# Sch1r2_new.net
KiCad netlist of a schematic drawn in EAGLE
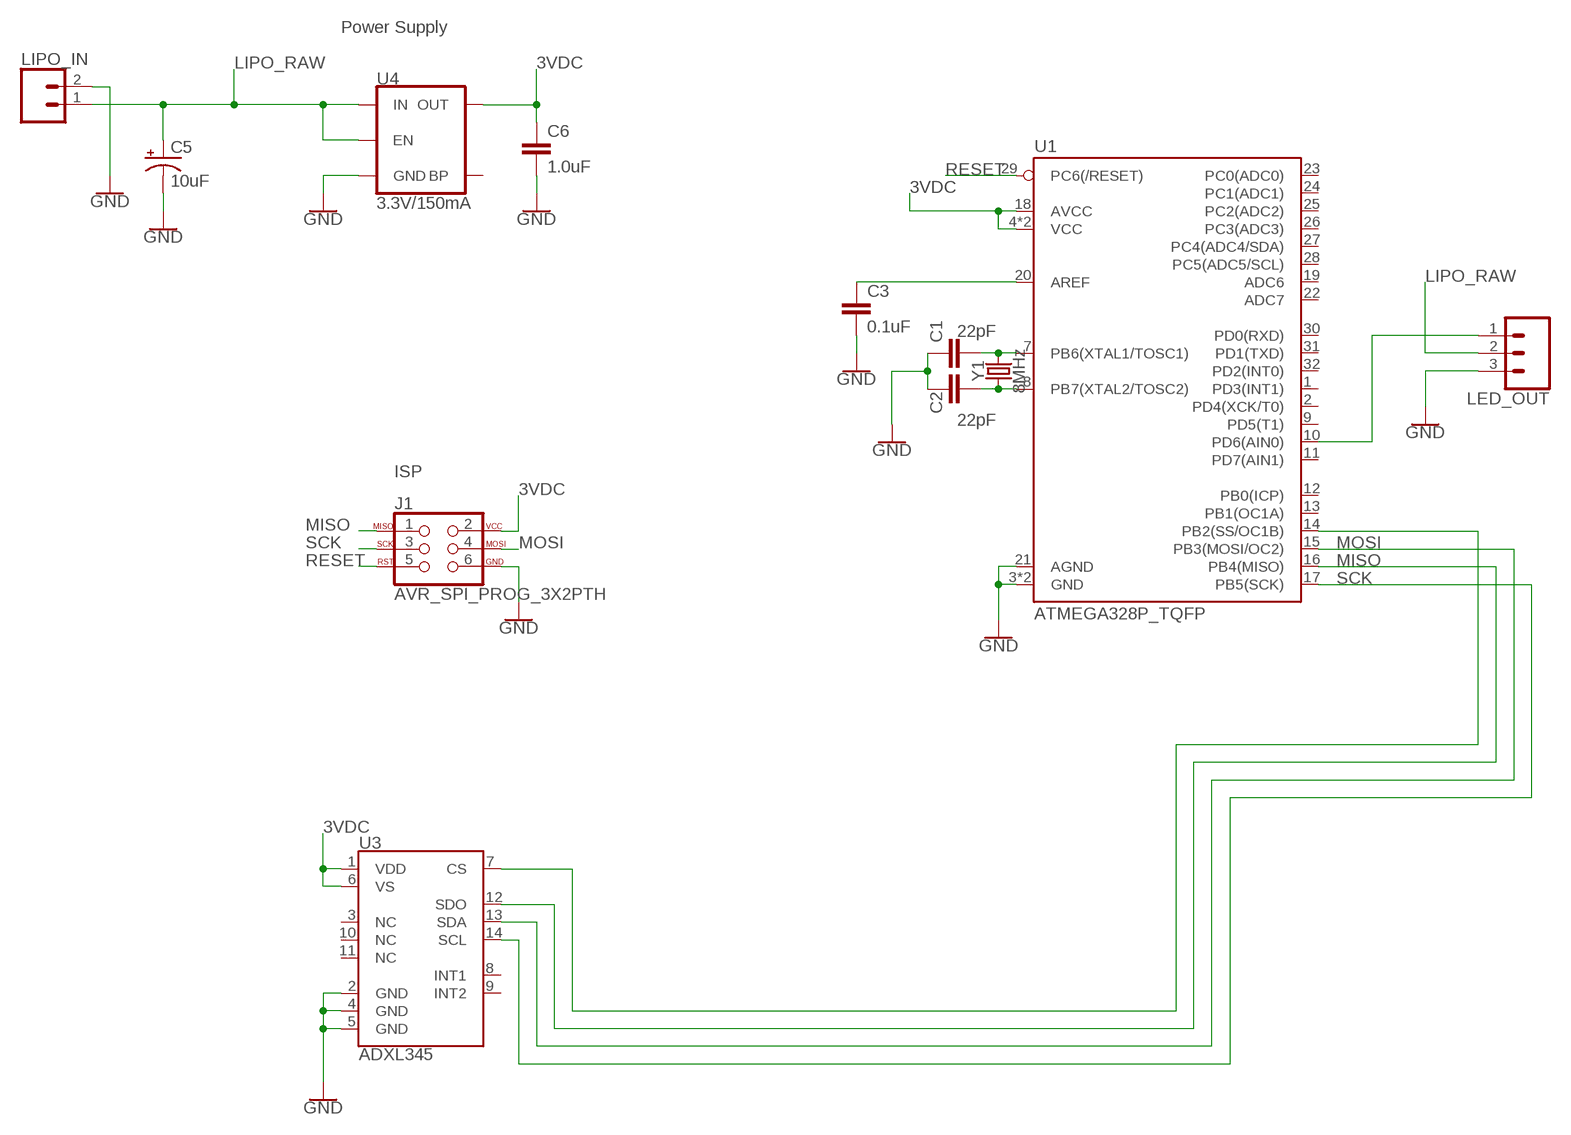
[diagram p0: schematic, sheet 1]

(export (version "E")
  (design (tool "Eeschema 10.0.6"))
  (components
    (comp (ref "C1")
      (value "22pF")
      (footprint "eagle-import:0603")
      (libsource (lib "eagle-import") (part "22PF-0603-50V-5%"))
    )
    (comp (ref "C2")
      (value "22pF")
      (footprint "eagle-import:0603")
      (libsource (lib "eagle-import") (part "22PF-0603-50V-5%"))
    )
    (comp (ref "C3")
      (value "0.1uF")
      (footprint "eagle-import:0402")
      (libsource (lib "eagle-import") (part "0.1UF-0402-16V-10%"))
    )
    (comp (ref "C5")
      (value "10uF")
      (footprint "eagle-import:0603-POLAR")
      (libsource (lib "eagle-import") (part "10UF-POLAR-0603-6.3V-20%(TANT)"))
    )
    (comp (ref "C6")
      (value "1.0uF")
      (footprint "eagle-import:0402")
      (libsource (lib "eagle-import") (part "1.0UF-0402-16V-10%"))
    )
    (comp (ref "J1")
      (value "AVR_SPI_PROG_3X2PTH")
      (footprint "eagle-import:2X3")
      (libsource (lib "eagle-import") (part "AVR_SPI_PROG_3X2PTH"))
    )
    (comp (ref "LED_OUT")
      (value "CONN_03LOCK_LONGPADS")
      (footprint "eagle-import:1X03_LOCK_LONGPADS")
      (libsource (lib "eagle-import") (part "CONN_03LOCK_LONGPADS"))
    )
    (comp (ref "LIPO_IN")
      (value "CONN_02PTH3")
      (footprint "eagle-import:1X02_LONGPADS")
      (libsource (lib "eagle-import") (part "CONN_02PTH3"))
    )
    (comp (ref "U1")
      (value "ATMEGA328P_TQFP")
      (footprint "eagle-import:TQFP32-08")
      (libsource (lib "eagle-import") (part "ATMEGA328P_TQFP"))
    )
    (comp (ref "U3")
      (value "ADXL345")
      (footprint "eagle-import:LGA-14")
      (libsource (lib "eagle-import") (part "ADXL345"))
    )
    (comp (ref "U4")
      (value "3.3V/150mA")
      (footprint "eagle-import:SOT23-5")
      (libsource (lib "eagle-import") (part "V_REG_MIC52053.3V"))
    )
    (comp (ref "Y1")
      (value "8MHz")
      (footprint "eagle-import:CRYSTAL-SMD-5X3.2-4PAD")
      (libsource (lib "eagle-import") (part "CRYSTAL-8MHZSMD-5X3.2"))
    )
  )
  (nets
    (net (code "1") (name "/3VDC") (class "Default")
      (node (ref "C6") (pin "1") (pinfunction "1_1") (pintype "passive"))
      (node (ref "J1") (pin "2") (pinfunction "2_2") (pintype "passive"))
      (node (ref "U1") (pin "18") (pinfunction "AVCC_18") (pintype "bidirectional"))
      (node (ref "U1") (pin "4") (pinfunction "VCC_4") (pintype "bidirectional"))
      (node (ref "U1") (pin "6") (pinfunction "VCC_6") (pintype "bidirectional"))
      (node (ref "U3") (pin "1") (pinfunction "VDD_1") (pintype "bidirectional"))
      (node (ref "U3") (pin "6") (pinfunction "VS_6") (pintype "bidirectional"))
      (node (ref "U4") (pin "5") (pinfunction "OUT_5") (pintype "passive"))
    )
    (net (code "2") (name "/LIPO_RAW") (class "Default")
      (node (ref "C5") (pin "+") (pinfunction "+_+") (pintype "passive"))
      (node (ref "LED_OUT") (pin "2") (pinfunction "2_2") (pintype "passive"))
      (node (ref "LIPO_IN") (pin "1") (pinfunction "1_1") (pintype "passive"))
      (node (ref "U4") (pin "1") (pinfunction "IN_1") (pintype "input"))
      (node (ref "U4") (pin "3") (pinfunction "EN_3") (pintype "input"))
    )
    (net (code "3") (name "/MISO") (class "Default")
      (node (ref "J1") (pin "1") (pinfunction "1_1") (pintype "passive"))
      (node (ref "U1") (pin "16") (pinfunction "PB4(MISO)_16") (pintype "bidirectional"))
      (node (ref "U3") (pin "12") (pinfunction "SDO_12") (pintype "bidirectional"))
    )
    (net (code "4") (name "/MOSI") (class "Default")
      (node (ref "J1") (pin "4") (pinfunction "4_4") (pintype "passive"))
      (node (ref "U1") (pin "15") (pinfunction "PB3(MOSI/OC2)_15") (pintype "bidirectional"))
      (node (ref "U3") (pin "13") (pinfunction "SDA_13") (pintype "bidirectional"))
    )
    (net (code "5") (name "/RESET") (class "Default")
      (node (ref "J1") (pin "5") (pinfunction "5_5") (pintype "passive"))
      (node (ref "U1") (pin "29") (pinfunction "PC6(/RESET)_29") (pintype "bidirectional"))
    )
    (net (code "6") (name "/SCK") (class "Default")
      (node (ref "J1") (pin "3") (pinfunction "3_3") (pintype "passive"))
      (node (ref "U1") (pin "17") (pinfunction "PB5(SCK)_17") (pintype "bidirectional"))
      (node (ref "U3") (pin "14") (pinfunction "SCL_14") (pintype "bidirectional"))
    )
    (net (code "7") (name "GND") (class "Default")
      (node (ref "C1") (pin "1") (pinfunction "1_1") (pintype "passive"))
      (node (ref "C2") (pin "1") (pinfunction "1_1") (pintype "passive"))
      (node (ref "C3") (pin "2") (pinfunction "2_2") (pintype "passive"))
      (node (ref "C5") (pin "-") (pinfunction "-_-") (pintype "passive"))
      (node (ref "C6") (pin "2") (pinfunction "2_2") (pintype "passive"))
      (node (ref "J1") (pin "6") (pinfunction "6_6") (pintype "passive"))
      (node (ref "LED_OUT") (pin "3") (pinfunction "3_3") (pintype "passive"))
      (node (ref "LIPO_IN") (pin "2") (pinfunction "2_2") (pintype "passive"))
      (node (ref "U1") (pin "21") (pinfunction "AGND_21") (pintype "bidirectional"))
      (node (ref "U1") (pin "3") (pinfunction "GND_3") (pintype "bidirectional"))
      (node (ref "U1") (pin "5") (pinfunction "GND_5") (pintype "bidirectional"))
      (node (ref "U3") (pin "2") (pinfunction "GND_2") (pintype "bidirectional"))
      (node (ref "U3") (pin "4") (pinfunction "GND_4") (pintype "bidirectional"))
      (node (ref "U3") (pin "5") (pinfunction "GND_5") (pintype "bidirectional"))
      (node (ref "U4") (pin "2") (pinfunction "GND_2") (pintype "input"))
    )
    (net (code "8") (name "Net-(U1-AREF)") (class "Default")
      (node (ref "C3") (pin "1") (pinfunction "1_1") (pintype "passive"))
      (node (ref "U1") (pin "20") (pinfunction "AREF_20") (pintype "bidirectional"))
    )
    (net (code "9") (name "Net-(U1-PB2(SS{slash}OC1B))") (class "Default")
      (node (ref "U1") (pin "14") (pinfunction "PB2(SS/OC1B)_14") (pintype "bidirectional"))
      (node (ref "U3") (pin "7") (pinfunction "CS_7") (pintype "bidirectional"))
    )
    (net (code "10") (name "Net-(U1-PB6(XTAL1{slash}TOSC1))") (class "Default")
      (node (ref "C1") (pin "2") (pinfunction "2_2") (pintype "passive"))
      (node (ref "U1") (pin "7") (pinfunction "PB6(XTAL1/TOSC1)_7") (pintype "bidirectional"))
      (node (ref "Y1") (pin "3") (pinfunction "2_3") (pintype "passive"))
    )
    (net (code "11") (name "Net-(U1-PB7(XTAL2{slash}TOSC2))") (class "Default")
      (node (ref "C2") (pin "2") (pinfunction "2_2") (pintype "passive"))
      (node (ref "U1") (pin "8") (pinfunction "PB7(XTAL2/TOSC2)_8") (pintype "bidirectional"))
      (node (ref "Y1") (pin "1") (pinfunction "1_1") (pintype "passive"))
    )
    (net (code "12") (name "Net-(U1-PD6(AIN0))") (class "Default")
      (node (ref "LED_OUT") (pin "1") (pinfunction "1_1") (pintype "passive"))
      (node (ref "U1") (pin "10") (pinfunction "PD6(AIN0)_10") (pintype "bidirectional"))
    )
    (net (code "13") (name "unconnected-(U1-ADC6-Pad19)") (class "Default")
      (node (ref "U1") (pin "19") (pinfunction "ADC6_19") (pintype "bidirectional"))
    )
    (net (code "14") (name "unconnected-(U1-ADC7-Pad22)") (class "Default")
      (node (ref "U1") (pin "22") (pinfunction "ADC7_22") (pintype "bidirectional"))
    )
    (net (code "15") (name "unconnected-(U1-PB0(ICP)-Pad12)") (class "Default")
      (node (ref "U1") (pin "12") (pinfunction "PB0(ICP)_12") (pintype "bidirectional"))
    )
    (net (code "16") (name "unconnected-(U1-PB1(OC1A)-Pad13)") (class "Default")
      (node (ref "U1") (pin "13") (pinfunction "PB1(OC1A)_13") (pintype "bidirectional"))
    )
    (net (code "17") (name "unconnected-(U1-PC0(ADC0)-Pad23)") (class "Default")
      (node (ref "U1") (pin "23") (pinfunction "PC0(ADC0)_23") (pintype "bidirectional"))
    )
    (net (code "18") (name "unconnected-(U1-PC1(ADC1)-Pad24)") (class "Default")
      (node (ref "U1") (pin "24") (pinfunction "PC1(ADC1)_24") (pintype "bidirectional"))
    )
    (net (code "19") (name "unconnected-(U1-PC2(ADC2)-Pad25)") (class "Default")
      (node (ref "U1") (pin "25") (pinfunction "PC2(ADC2)_25") (pintype "bidirectional"))
    )
    (net (code "20") (name "unconnected-(U1-PC3(ADC3)-Pad26)") (class "Default")
      (node (ref "U1") (pin "26") (pinfunction "PC3(ADC3)_26") (pintype "bidirectional"))
    )
    (net (code "21") (name "unconnected-(U1-PC4(ADC4{slash}SDA)-Pad27)") (class "Default")
      (node (ref "U1") (pin "27") (pinfunction "PC4(ADC4/SDA)_27") (pintype "bidirectional"))
    )
    (net (code "22") (name "unconnected-(U1-PC5(ADC5{slash}SCL)-Pad28)") (class "Default")
      (node (ref "U1") (pin "28") (pinfunction "PC5(ADC5/SCL)_28") (pintype "bidirectional"))
    )
    (net (code "23") (name "unconnected-(U1-PD0(RXD)-Pad30)") (class "Default")
      (node (ref "U1") (pin "30") (pinfunction "PD0(RXD)_30") (pintype "bidirectional"))
    )
    (net (code "24") (name "unconnected-(U1-PD1(TXD)-Pad31)") (class "Default")
      (node (ref "U1") (pin "31") (pinfunction "PD1(TXD)_31") (pintype "bidirectional"))
    )
    (net (code "25") (name "unconnected-(U1-PD2(INT0)-Pad32)") (class "Default")
      (node (ref "U1") (pin "32") (pinfunction "PD2(INT0)_32") (pintype "bidirectional"))
    )
    (net (code "26") (name "unconnected-(U1-PD3(INT1)-Pad1)") (class "Default")
      (node (ref "U1") (pin "1") (pinfunction "PD3(INT1)_1") (pintype "bidirectional"))
    )
    (net (code "27") (name "unconnected-(U1-PD4(XCK{slash}T0)-Pad2)") (class "Default")
      (node (ref "U1") (pin "2") (pinfunction "PD4(XCK/T0)_2") (pintype "bidirectional"))
    )
    (net (code "28") (name "unconnected-(U1-PD5(T1)-Pad9)") (class "Default")
      (node (ref "U1") (pin "9") (pinfunction "PD5(T1)_9") (pintype "bidirectional"))
    )
    (net (code "29") (name "unconnected-(U1-PD7(AIN1)-Pad11)") (class "Default")
      (node (ref "U1") (pin "11") (pinfunction "PD7(AIN1)_11") (pintype "bidirectional"))
    )
    (net (code "30") (name "unconnected-(U3-INT1-Pad8)") (class "Default")
      (node (ref "U3") (pin "8") (pinfunction "INT1_8") (pintype "bidirectional"))
    )
    (net (code "31") (name "unconnected-(U3-INT2-Pad9)") (class "Default")
      (node (ref "U3") (pin "9") (pinfunction "INT2_9") (pintype "bidirectional"))
    )
    (net (code "32") (name "unconnected-(U3-NC-Pad3)") (class "Default")
      (node (ref "U3") (pin "3") (pinfunction "NC_3") (pintype "bidirectional"))
    )
    (net (code "33") (name "unconnected-(U3-NC-Pad10)") (class "Default")
      (node (ref "U3") (pin "10") (pinfunction "NC_10") (pintype "bidirectional"))
    )
    (net (code "34") (name "unconnected-(U3-NC-Pad11)") (class "Default")
      (node (ref "U3") (pin "11") (pinfunction "NC_11") (pintype "bidirectional"))
    )
    (net (code "35") (name "unconnected-(U4-BP-Pad4)") (class "Default")
      (node (ref "U4") (pin "4") (pinfunction "BP_4") (pintype "input"))
    )
  )
)
